# theremin-shield.net
KiCad netlist of a schematic drawn in EAGLE
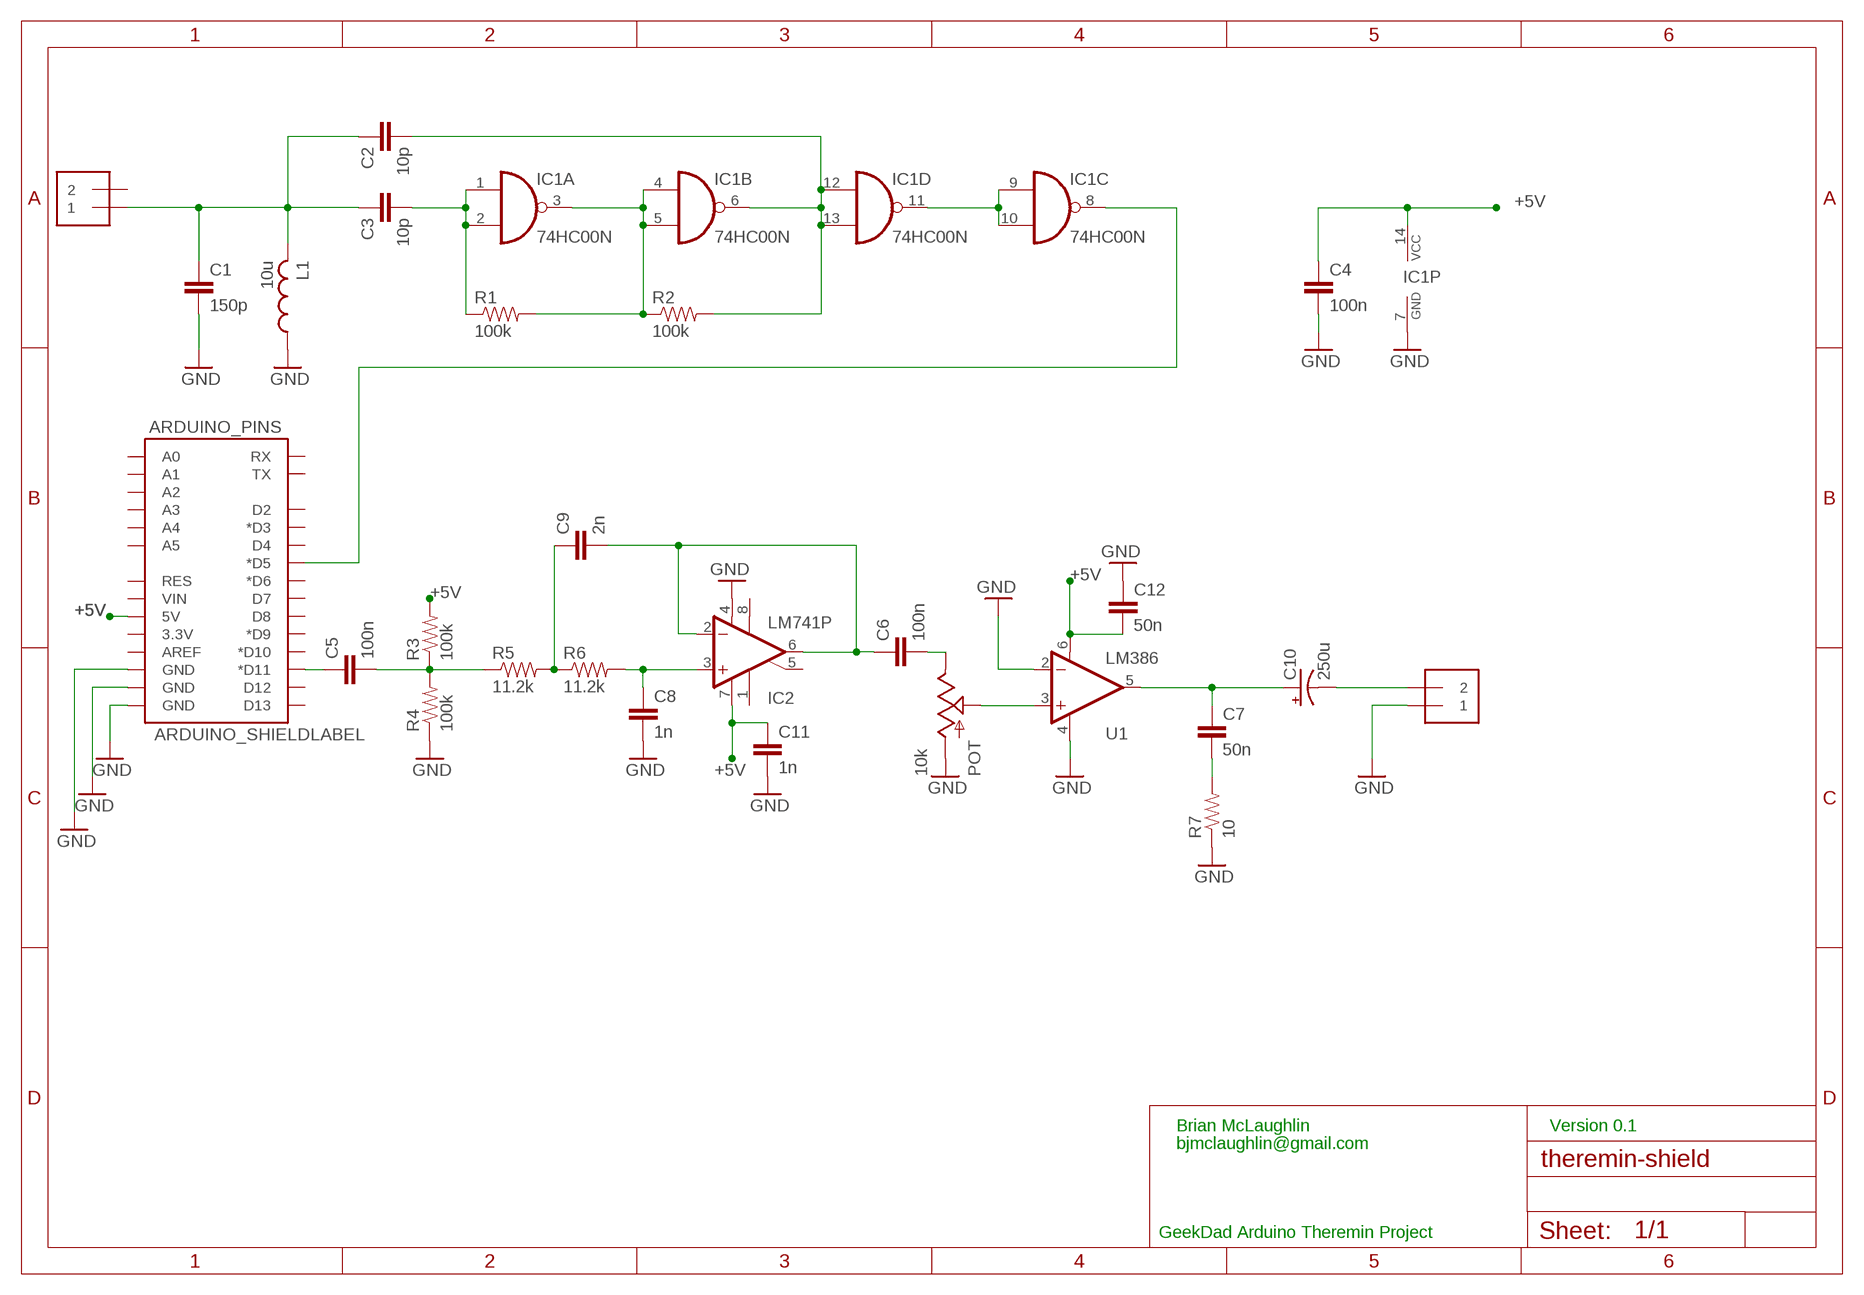
[diagram p0: schematic, sheet 1]

(export (version "E")
  (design (tool "Eeschema 10.0.6"))
  (components
    (comp (ref "ARDUINO_PINS")
      (value "ARDUINO_SHIELDLABEL")
      (footprint "eagle-import:DUEMILANOVE_SHIELD")
      (libsource (lib "eagle-import") (part "ARDUINO_SHIELDLABEL"))
    )
    (comp (ref "C1")
      (value "150p")
      (footprint "eagle-import:CAP-PTH-SMALL")
      (libsource (lib "eagle-import") (part "CAPPTH"))
    )
    (comp (ref "C2")
      (value "10p")
      (footprint "eagle-import:CAP-PTH-SMALL")
      (libsource (lib "eagle-import") (part "CAPPTH"))
    )
    (comp (ref "C3")
      (value "10p")
      (footprint "eagle-import:CAP-PTH-SMALL")
      (libsource (lib "eagle-import") (part "CAPPTH"))
    )
    (comp (ref "C4")
      (value "100n")
      (footprint "eagle-import:CAP-PTH-SMALL")
      (libsource (lib "eagle-import") (part "CAPPTH"))
    )
    (comp (ref "C5")
      (value "100n")
      (footprint "eagle-import:CAP-PTH-LARGE")
      (libsource (lib "eagle-import") (part "CAPPTH3"))
    )
    (comp (ref "C6")
      (value "100n")
      (footprint "eagle-import:CAP-PTH-LARGE")
      (libsource (lib "eagle-import") (part "CAPPTH3"))
    )
    (comp (ref "C7")
      (value "50n")
      (footprint "eagle-import:CAP-PTH-SMALL2")
      (libsource (lib "eagle-import") (part "CAPPTH2"))
    )
    (comp (ref "C8")
      (value "1n")
      (footprint "eagle-import:CAP-PTH-SMALL2")
      (libsource (lib "eagle-import") (part "CAPPTH2"))
    )
    (comp (ref "C9")
      (value "2n")
      (footprint "eagle-import:CAP-PTH-SMALL2")
      (libsource (lib "eagle-import") (part "CAPPTH2"))
    )
    (comp (ref "C10")
      (value "250u")
      (footprint "eagle-import:CPOL-RADIAL-1000UF-25V")
      (libsource (lib "eagle-import") (part "CAP_POLPTH4"))
    )
    (comp (ref "C11")
      (value "1n")
      (footprint "eagle-import:CAP-PTH-SMALL2")
      (libsource (lib "eagle-import") (part "CAPPTH2"))
    )
    (comp (ref "C12")
      (value "50n")
      (footprint "eagle-import:CAP-PTH-SMALL2")
      (libsource (lib "eagle-import") (part "CAPPTH2"))
    )
    (comp (ref "IC1")
      (value "74HC00N")
      (footprint "eagle-import:DIL14")
      (libsource (lib "eagle-import") (part "7400NHC"))
    )
    (comp (ref "IC2")
      (value "LM741P")
      (footprint "eagle-import:DIL08")
      (libsource (lib "eagle-import") (part "741PLM"))
    )
    (comp (ref "J1")
      (value "1X2-3.5MM")
      (footprint "eagle-import:1X2-3.5MM")
      (libsource (lib "eagle-import") (part "1X2-3.5MM"))
    )
    (comp (ref "J2")
      (value "1X2-3.5MM")
      (footprint "eagle-import:1X2-3.5MM")
      (libsource (lib "eagle-import") (part "1X2-3.5MM"))
    )
    (comp (ref "L1")
      (value "10u")
      (footprint "eagle-import:0204_7")
      (libsource (lib "eagle-import") (part "L-US0204/7"))
    )
    (comp (ref "POT")
      (value "10k")
      (footprint "eagle-import:ALPS_POT")
      (libsource (lib "eagle-import") (part "POT"))
    )
    (comp (ref "R1")
      (value "100k")
      (footprint "eagle-import:AXIAL-0.4")
      (libsource (lib "eagle-import") (part "RESISTORPTH-1/4W"))
    )
    (comp (ref "R2")
      (value "100k")
      (footprint "eagle-import:AXIAL-0.4")
      (libsource (lib "eagle-import") (part "RESISTORPTH-1/4W"))
    )
    (comp (ref "R3")
      (value "100k")
      (footprint "eagle-import:AXIAL-0.4")
      (libsource (lib "eagle-import") (part "RESISTORPTH-1/4W"))
    )
    (comp (ref "R4")
      (value "100k")
      (footprint "eagle-import:AXIAL-0.4")
      (libsource (lib "eagle-import") (part "RESISTORPTH-1/4W"))
    )
    (comp (ref "R5")
      (value "11.2k")
      (footprint "eagle-import:AXIAL-0.4")
      (libsource (lib "eagle-import") (part "RESISTORPTH-1/4W"))
    )
    (comp (ref "R6")
      (value "11.2k")
      (footprint "eagle-import:AXIAL-0.4")
      (libsource (lib "eagle-import") (part "RESISTORPTH-1/4W"))
    )
    (comp (ref "R7")
      (value "10")
      (footprint "eagle-import:AXIAL-0.4")
      (libsource (lib "eagle-import") (part "RESISTORPTH-1/4W"))
    )
    (comp (ref "U1")
      (value "LM386")
      (footprint "eagle-import:DIP08")
      (libsource (lib "eagle-import") (part "LM386"))
    )
  )
  (nets
    (net (code "1") (name "/+5V") (class "Default")
      (node (ref "ARDUINO_PINS") (pin "5V") (pinfunction "5V_5V") (pintype "bidirectional"))
      (node (ref "C11") (pin "1") (pinfunction "1_1") (pintype "passive"))
      (node (ref "C12") (pin "2") (pinfunction "2_2") (pintype "passive"))
      (node (ref "C4") (pin "1") (pinfunction "1_1") (pintype "passive"))
      (node (ref "IC1") (pin "14") (pinfunction "VCC_14") (pintype "power_in"))
      (node (ref "IC2") (pin "7") (pinfunction "V+_7") (pintype "power_in"))
      (node (ref "R3") (pin "P$2") (pinfunction "2_P$2") (pintype "passive"))
      (node (ref "U1") (pin "6") (pinfunction "V+_6") (pintype "power_in"))
    )
    (net (code "2") (name "GND") (class "Default")
      (node (ref "ARDUINO_PINS") (pin "GND@0") (pinfunction "GND_GND@0") (pintype "bidirectional"))
      (node (ref "ARDUINO_PINS") (pin "GND@1") (pinfunction "GND_GND@1") (pintype "bidirectional"))
      (node (ref "ARDUINO_PINS") (pin "GND@2") (pinfunction "GND_GND@2") (pintype "bidirectional"))
      (node (ref "C1") (pin "2") (pinfunction "2_2") (pintype "passive"))
      (node (ref "C11") (pin "2") (pinfunction "2_2") (pintype "passive"))
      (node (ref "C12") (pin "1") (pinfunction "1_1") (pintype "passive"))
      (node (ref "C4") (pin "2") (pinfunction "2_2") (pintype "passive"))
      (node (ref "C8") (pin "2") (pinfunction "2_2") (pintype "passive"))
      (node (ref "IC1") (pin "7") (pinfunction "GND_7") (pintype "power_in"))
      (node (ref "IC2") (pin "4") (pinfunction "V-_4") (pintype "power_in"))
      (node (ref "J1") (pin "1") (pinfunction "1_1") (pintype "passive"))
      (node (ref "L1") (pin "1") (pinfunction "1_1") (pintype "passive"))
      (node (ref "POT") (pin "P$3") (pinfunction "A_P$3") (pintype "passive"))
      (node (ref "R4") (pin "P$1") (pinfunction "1_P$1") (pintype "passive"))
      (node (ref "R7") (pin "P$1") (pinfunction "1_P$1") (pintype "passive"))
      (node (ref "U1") (pin "2") (pinfunction "-IN_2") (pintype "input"))
      (node (ref "U1") (pin "4") (pinfunction "V-_4") (pintype "power_in"))
    )
    (net (code "3") (name "Net-(ARDUINO_PINS-*D5)") (class "Default")
      (node (ref "ARDUINO_PINS") (pin "D5") (pinfunction "*D5_D5") (pintype "bidirectional"))
      (node (ref "IC1") (pin "8") (pinfunction "O_8") (pintype "output"))
    )
    (net (code "4") (name "Net-(ARDUINO_PINS-*D11)") (class "Default")
      (node (ref "ARDUINO_PINS") (pin "D11") (pinfunction "*D11_D11") (pintype "bidirectional"))
      (node (ref "C5") (pin "1") (pinfunction "1_1") (pintype "passive"))
    )
    (net (code "5") (name "Net-(C1-Pad1)") (class "Default")
      (node (ref "C1") (pin "1") (pinfunction "1_1") (pintype "passive"))
      (node (ref "C2") (pin "1") (pinfunction "1_1") (pintype "passive"))
      (node (ref "C3") (pin "1") (pinfunction "1_1") (pintype "passive"))
      (node (ref "J2") (pin "1") (pinfunction "1_1") (pintype "passive"))
      (node (ref "L1") (pin "2") (pinfunction "2_2") (pintype "passive"))
    )
    (net (code "6") (name "Net-(C10-+)") (class "Default")
      (node (ref "C10") (pin "1") (pinfunction "+_1") (pintype "passive"))
      (node (ref "C7") (pin "1") (pinfunction "1_1") (pintype "passive"))
      (node (ref "U1") (pin "5") (pinfunction "OUT_5") (pintype "output"))
    )
    (net (code "7") (name "Net-(C10--)") (class "Default")
      (node (ref "C10") (pin "2") (pinfunction "-_2") (pintype "passive"))
      (node (ref "J1") (pin "2") (pinfunction "2_2") (pintype "passive"))
    )
    (net (code "8") (name "Net-(IC1A-I0)") (class "Default")
      (node (ref "C3") (pin "2") (pinfunction "2_2") (pintype "passive"))
      (node (ref "IC1") (pin "1") (pinfunction "I0_1") (pintype "input"))
      (node (ref "IC1") (pin "2") (pinfunction "I1_2") (pintype "input"))
      (node (ref "R1") (pin "P$1") (pinfunction "1_P$1") (pintype "passive"))
    )
    (net (code "9") (name "Net-(IC1A-O)") (class "Default")
      (node (ref "IC1") (pin "3") (pinfunction "O_3") (pintype "output"))
      (node (ref "IC1") (pin "4") (pinfunction "I0_4") (pintype "input"))
      (node (ref "IC1") (pin "5") (pinfunction "I1_5") (pintype "input"))
      (node (ref "R1") (pin "P$2") (pinfunction "2_P$2") (pintype "passive"))
      (node (ref "R2") (pin "P$1") (pinfunction "1_P$1") (pintype "passive"))
    )
    (net (code "10") (name "Net-(IC1B-O)") (class "Default")
      (node (ref "C2") (pin "2") (pinfunction "2_2") (pintype "passive"))
      (node (ref "IC1") (pin "12") (pinfunction "I0_12") (pintype "input"))
      (node (ref "IC1") (pin "13") (pinfunction "I1_13") (pintype "input"))
      (node (ref "IC1") (pin "6") (pinfunction "O_6") (pintype "output"))
      (node (ref "R2") (pin "P$2") (pinfunction "2_P$2") (pintype "passive"))
    )
    (net (code "11") (name "Net-(IC1C-I0)") (class "Default")
      (node (ref "IC1") (pin "10") (pinfunction "I1_10") (pintype "input"))
      (node (ref "IC1") (pin "11") (pinfunction "O_11") (pintype "output"))
      (node (ref "IC1") (pin "9") (pinfunction "I0_9") (pintype "input"))
    )
    (net (code "12") (name "Net-(IC2-+IN)") (class "Default")
      (node (ref "C8") (pin "1") (pinfunction "1_1") (pintype "passive"))
      (node (ref "IC2") (pin "3") (pinfunction "+IN_3") (pintype "input"))
      (node (ref "R6") (pin "P$2") (pinfunction "2_P$2") (pintype "passive"))
    )
    (net (code "13") (name "Net-(IC2--IN)") (class "Default")
      (node (ref "C6") (pin "1") (pinfunction "1_1") (pintype "passive"))
      (node (ref "C9") (pin "2") (pinfunction "2_2") (pintype "passive"))
      (node (ref "IC2") (pin "2") (pinfunction "-IN_2") (pintype "input"))
      (node (ref "IC2") (pin "6") (pinfunction "OUT_6") (pintype "output"))
    )
    (net (code "14") (name "Net-(POT-E)") (class "Default")
      (node (ref "C6") (pin "2") (pinfunction "2_2") (pintype "passive"))
      (node (ref "POT") (pin "P$1") (pinfunction "E_P$1") (pintype "passive"))
    )
    (net (code "15") (name "Net-(POT-S)") (class "Default")
      (node (ref "POT") (pin "P$2") (pinfunction "S_P$2") (pintype "passive"))
      (node (ref "U1") (pin "3") (pinfunction "+IN_3") (pintype "input"))
    )
    (net (code "16") (name "Net-(R3-1)") (class "Default")
      (node (ref "C5") (pin "2") (pinfunction "2_2") (pintype "passive"))
      (node (ref "R3") (pin "P$1") (pinfunction "1_P$1") (pintype "passive"))
      (node (ref "R4") (pin "P$2") (pinfunction "2_P$2") (pintype "passive"))
      (node (ref "R5") (pin "P$1") (pinfunction "1_P$1") (pintype "passive"))
    )
    (net (code "17") (name "Net-(R5-2)") (class "Default")
      (node (ref "C9") (pin "1") (pinfunction "1_1") (pintype "passive"))
      (node (ref "R5") (pin "P$2") (pinfunction "2_P$2") (pintype "passive"))
      (node (ref "R6") (pin "P$1") (pinfunction "1_P$1") (pintype "passive"))
    )
    (net (code "18") (name "Net-(R7-2)") (class "Default")
      (node (ref "C7") (pin "2") (pinfunction "2_2") (pintype "passive"))
      (node (ref "R7") (pin "P$2") (pinfunction "2_P$2") (pintype "passive"))
    )
    (net (code "19") (name "unconnected-(ARDUINO_PINS-*D3-PadD3)") (class "Default")
      (node (ref "ARDUINO_PINS") (pin "D3") (pinfunction "*D3_D3") (pintype "bidirectional"))
    )
    (net (code "20") (name "unconnected-(ARDUINO_PINS-*D6-PadD6)") (class "Default")
      (node (ref "ARDUINO_PINS") (pin "D6") (pinfunction "*D6_D6") (pintype "bidirectional"))
    )
    (net (code "21") (name "unconnected-(ARDUINO_PINS-*D9-PadD9)") (class "Default")
      (node (ref "ARDUINO_PINS") (pin "D9") (pinfunction "*D9_D9") (pintype "bidirectional"))
    )
    (net (code "22") (name "unconnected-(ARDUINO_PINS-*D10-PadD10)") (class "Default")
      (node (ref "ARDUINO_PINS") (pin "D10") (pinfunction "*D10_D10") (pintype "bidirectional"))
    )
    (net (code "23") (name "unconnected-(ARDUINO_PINS-Pad3.3V)") (class "Default")
      (node (ref "ARDUINO_PINS") (pin "3.3V") (pinfunction "3.3V_3.3V") (pintype "bidirectional"))
    )
    (net (code "24") (name "unconnected-(ARDUINO_PINS-PadA0)") (class "Default")
      (node (ref "ARDUINO_PINS") (pin "A0") (pinfunction "A0_A0") (pintype "bidirectional"))
    )
    (net (code "25") (name "unconnected-(ARDUINO_PINS-PadA1)") (class "Default")
      (node (ref "ARDUINO_PINS") (pin "A1") (pinfunction "A1_A1") (pintype "bidirectional"))
    )
    (net (code "26") (name "unconnected-(ARDUINO_PINS-PadA2)") (class "Default")
      (node (ref "ARDUINO_PINS") (pin "A2") (pinfunction "A2_A2") (pintype "bidirectional"))
    )
    (net (code "27") (name "unconnected-(ARDUINO_PINS-PadA3)") (class "Default")
      (node (ref "ARDUINO_PINS") (pin "A3") (pinfunction "A3_A3") (pintype "bidirectional"))
    )
    (net (code "28") (name "unconnected-(ARDUINO_PINS-PadA4)") (class "Default")
      (node (ref "ARDUINO_PINS") (pin "A4") (pinfunction "A4_A4") (pintype "bidirectional"))
    )
    (net (code "29") (name "unconnected-(ARDUINO_PINS-PadA5)") (class "Default")
      (node (ref "ARDUINO_PINS") (pin "A5") (pinfunction "A5_A5") (pintype "bidirectional"))
    )
    (net (code "30") (name "unconnected-(ARDUINO_PINS-PadAREF)") (class "Default")
      (node (ref "ARDUINO_PINS") (pin "AREF") (pinfunction "AREF_AREF") (pintype "bidirectional"))
    )
    (net (code "31") (name "unconnected-(ARDUINO_PINS-PadD2)") (class "Default")
      (node (ref "ARDUINO_PINS") (pin "D2") (pinfunction "D2_D2") (pintype "bidirectional"))
    )
    (net (code "32") (name "unconnected-(ARDUINO_PINS-PadD4)") (class "Default")
      (node (ref "ARDUINO_PINS") (pin "D4") (pinfunction "D4_D4") (pintype "bidirectional"))
    )
    (net (code "33") (name "unconnected-(ARDUINO_PINS-PadD7)") (class "Default")
      (node (ref "ARDUINO_PINS") (pin "D7") (pinfunction "D7_D7") (pintype "bidirectional"))
    )
    (net (code "34") (name "unconnected-(ARDUINO_PINS-PadD8)") (class "Default")
      (node (ref "ARDUINO_PINS") (pin "D8") (pinfunction "D8_D8") (pintype "bidirectional"))
    )
    (net (code "35") (name "unconnected-(ARDUINO_PINS-PadD12)") (class "Default")
      (node (ref "ARDUINO_PINS") (pin "D12") (pinfunction "D12_D12") (pintype "bidirectional"))
    )
    (net (code "36") (name "unconnected-(ARDUINO_PINS-PadD13)") (class "Default")
      (node (ref "ARDUINO_PINS") (pin "D13") (pinfunction "D13_D13") (pintype "bidirectional"))
    )
    (net (code "37") (name "unconnected-(ARDUINO_PINS-PadRES)") (class "Default")
      (node (ref "ARDUINO_PINS") (pin "RES") (pinfunction "RES_RES") (pintype "bidirectional"))
    )
    (net (code "38") (name "unconnected-(ARDUINO_PINS-PadRX)") (class "Default")
      (node (ref "ARDUINO_PINS") (pin "RX") (pinfunction "RX_RX") (pintype "bidirectional"))
    )
    (net (code "39") (name "unconnected-(ARDUINO_PINS-PadTX)") (class "Default")
      (node (ref "ARDUINO_PINS") (pin "TX") (pinfunction "TX_TX") (pintype "bidirectional"))
    )
    (net (code "40") (name "unconnected-(ARDUINO_PINS-PadVIN)") (class "Default")
      (node (ref "ARDUINO_PINS") (pin "VIN") (pinfunction "VIN_VIN") (pintype "bidirectional"))
    )
    (net (code "41") (name "unconnected-(IC2-ON1-Pad1)") (class "Default")
      (node (ref "IC2") (pin "1") (pinfunction "ON1_1") (pintype "passive"))
    )
    (net (code "42") (name "unconnected-(IC2-ON2-Pad5)") (class "Default")
      (node (ref "IC2") (pin "5") (pinfunction "ON2_5") (pintype "passive"))
    )
    (net (code "43") (name "unconnected-(IC2-OPT-Pad8)") (class "Default")
      (node (ref "IC2") (pin "8") (pinfunction "OPT_8") (pintype "passive"))
    )
    (net (code "44") (name "unconnected-(J2-Pad2)") (class "Default")
      (node (ref "J2") (pin "2") (pinfunction "2_2") (pintype "passive"))
    )
  )
)
